# main.net
KiCad netlist of a schematic drawn in EAGLE
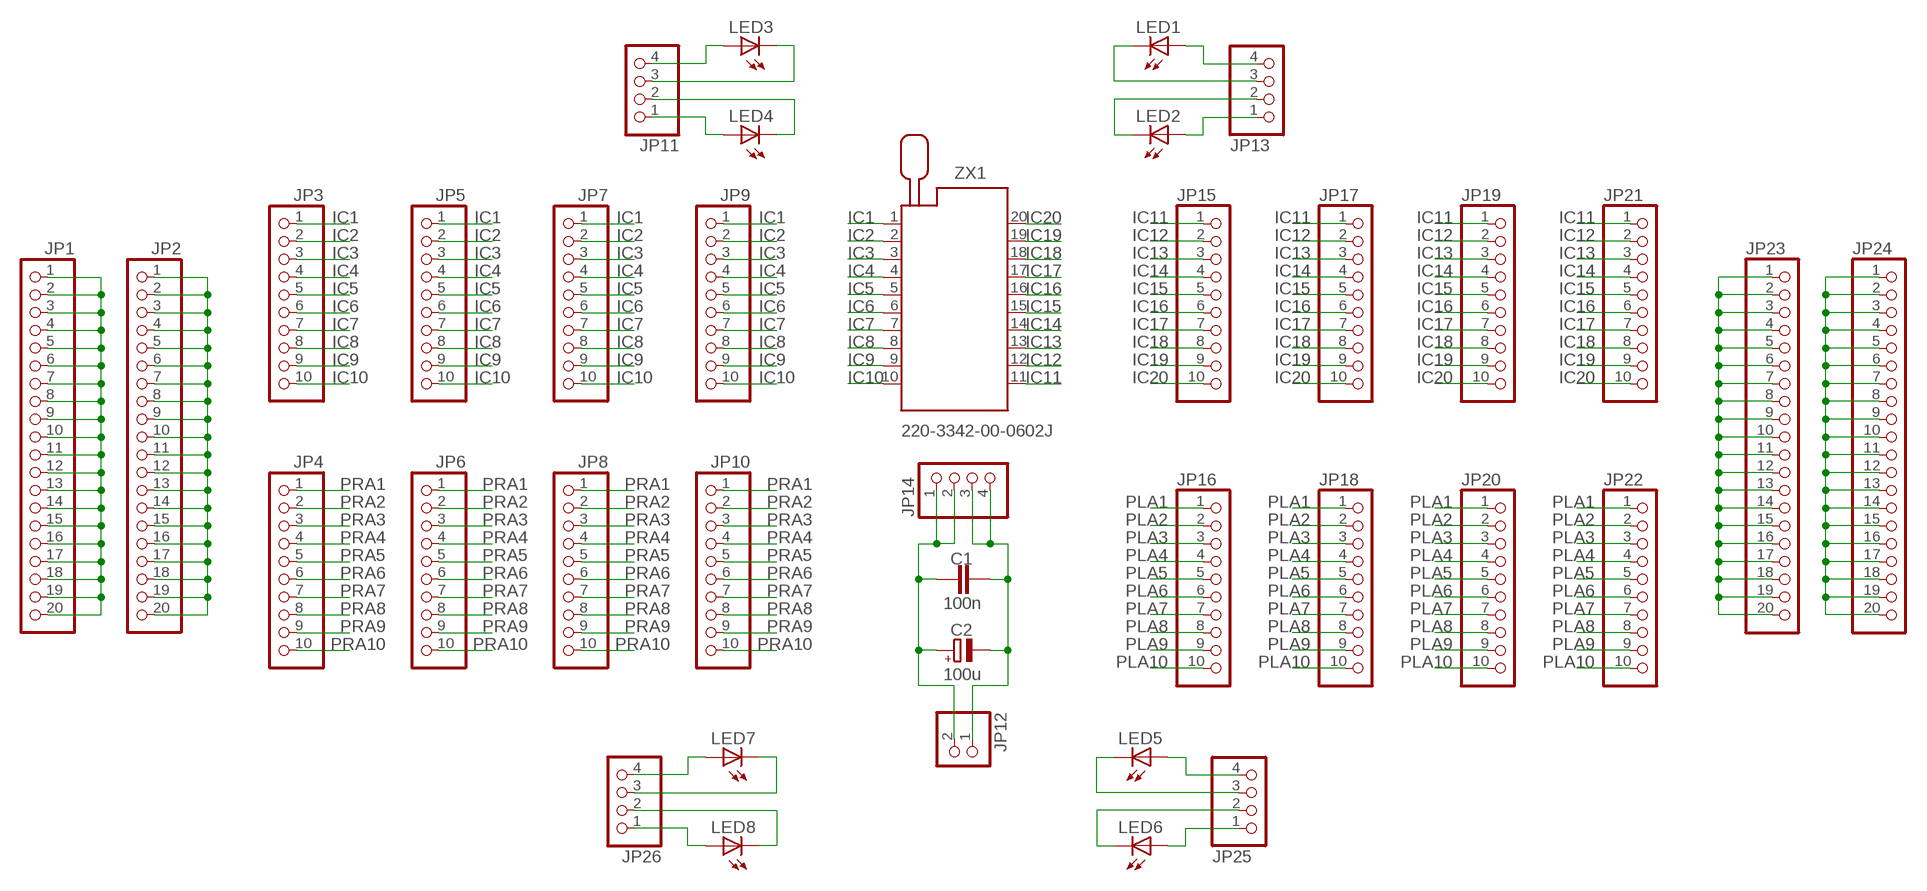
[diagram p0: schematic, sheet 1]

(export (version "E")
  (design (tool "Eeschema 10.0.6"))
  (components
    (comp (ref "C1")
      (value "100n")
      (footprint "eagle-import:C1206")
      (libsource (lib "eagle-import") (part "C-EUC1206"))
    )
    (comp (ref "C2")
      (value "100u")
      (footprint "eagle-import:SMC_A")
      (libsource (lib "eagle-import") (part "CPOL-EUSMCA"))
    )
    (comp (ref "JP1")
      (value "PINHD-1X20")
      (footprint "eagle-import:1X20")
      (libsource (lib "eagle-import") (part "PINHD-1X20"))
    )
    (comp (ref "JP2")
      (value "PINHD-1X20")
      (footprint "eagle-import:1X20")
      (libsource (lib "eagle-import") (part "PINHD-1X20"))
    )
    (comp (ref "JP3")
      (value "PINHD-1X10")
      (footprint "eagle-import:1X10")
      (libsource (lib "eagle-import") (part "PINHD-1X10"))
    )
    (comp (ref "JP4")
      (value "PINHD-1X10")
      (footprint "eagle-import:1X10")
      (libsource (lib "eagle-import") (part "PINHD-1X10"))
    )
    (comp (ref "JP5")
      (value "PINHD-1X10")
      (footprint "eagle-import:1X10")
      (libsource (lib "eagle-import") (part "PINHD-1X10"))
    )
    (comp (ref "JP6")
      (value "PINHD-1X10")
      (footprint "eagle-import:1X10")
      (libsource (lib "eagle-import") (part "PINHD-1X10"))
    )
    (comp (ref "JP7")
      (value "PINHD-1X10")
      (footprint "eagle-import:1X10")
      (libsource (lib "eagle-import") (part "PINHD-1X10"))
    )
    (comp (ref "JP8")
      (value "PINHD-1X10")
      (footprint "eagle-import:1X10")
      (libsource (lib "eagle-import") (part "PINHD-1X10"))
    )
    (comp (ref "JP9")
      (value "PINHD-1X10")
      (footprint "eagle-import:1X10")
      (libsource (lib "eagle-import") (part "PINHD-1X10"))
    )
    (comp (ref "JP10")
      (value "PINHD-1X10")
      (footprint "eagle-import:1X10")
      (libsource (lib "eagle-import") (part "PINHD-1X10"))
    )
    (comp (ref "JP11")
      (value "PINHD-1X4")
      (footprint "eagle-import:1X04")
      (libsource (lib "eagle-import") (part "PINHD-1X4"))
    )
    (comp (ref "JP12")
      (value "PINHD-1X2/90")
      (footprint "eagle-import:1X02_90")
      (libsource (lib "eagle-import") (part "PINHD-1X2/90"))
    )
    (comp (ref "JP13")
      (value "PINHD-1X4")
      (footprint "eagle-import:1X04")
      (libsource (lib "eagle-import") (part "PINHD-1X4"))
    )
    (comp (ref "JP14")
      (value "PINHD-1X4")
      (footprint "eagle-import:1X04")
      (libsource (lib "eagle-import") (part "PINHD-1X4"))
    )
    (comp (ref "JP15")
      (value "PINHD-1X10")
      (footprint "eagle-import:1X10")
      (libsource (lib "eagle-import") (part "PINHD-1X10"))
    )
    (comp (ref "JP16")
      (value "PINHD-1X10")
      (footprint "eagle-import:1X10")
      (libsource (lib "eagle-import") (part "PINHD-1X10"))
    )
    (comp (ref "JP17")
      (value "PINHD-1X10")
      (footprint "eagle-import:1X10")
      (libsource (lib "eagle-import") (part "PINHD-1X10"))
    )
    (comp (ref "JP18")
      (value "PINHD-1X10")
      (footprint "eagle-import:1X10")
      (libsource (lib "eagle-import") (part "PINHD-1X10"))
    )
    (comp (ref "JP19")
      (value "PINHD-1X10")
      (footprint "eagle-import:1X10")
      (libsource (lib "eagle-import") (part "PINHD-1X10"))
    )
    (comp (ref "JP20")
      (value "PINHD-1X10")
      (footprint "eagle-import:1X10")
      (libsource (lib "eagle-import") (part "PINHD-1X10"))
    )
    (comp (ref "JP21")
      (value "PINHD-1X10")
      (footprint "eagle-import:1X10")
      (libsource (lib "eagle-import") (part "PINHD-1X10"))
    )
    (comp (ref "JP22")
      (value "PINHD-1X10")
      (footprint "eagle-import:1X10")
      (libsource (lib "eagle-import") (part "PINHD-1X10"))
    )
    (comp (ref "JP23")
      (value "PINHD-1X20")
      (footprint "eagle-import:1X20")
      (libsource (lib "eagle-import") (part "PINHD-1X20"))
    )
    (comp (ref "JP24")
      (value "PINHD-1X20")
      (footprint "eagle-import:1X20")
      (libsource (lib "eagle-import") (part "PINHD-1X20"))
    )
    (comp (ref "JP25")
      (value "PINHD-1X4")
      (footprint "eagle-import:1X04")
      (libsource (lib "eagle-import") (part "PINHD-1X4"))
    )
    (comp (ref "JP26")
      (value "PINHD-1X4")
      (footprint "eagle-import:1X04")
      (libsource (lib "eagle-import") (part "PINHD-1X4"))
    )
    (comp (ref "LED1")
      (value "LEDSFH482")
      (footprint "eagle-import:SFH482")
      (libsource (lib "eagle-import") (part "LEDSFH482"))
    )
    (comp (ref "LED2")
      (value "LEDSFH482")
      (footprint "eagle-import:SFH482")
      (libsource (lib "eagle-import") (part "LEDSFH482"))
    )
    (comp (ref "LED3")
      (value "LEDSFH482")
      (footprint "eagle-import:SFH482")
      (libsource (lib "eagle-import") (part "LEDSFH482"))
    )
    (comp (ref "LED4")
      (value "LEDSFH482")
      (footprint "eagle-import:SFH482")
      (libsource (lib "eagle-import") (part "LEDSFH482"))
    )
    (comp (ref "LED5")
      (value "LEDSFH482")
      (footprint "eagle-import:SFH482")
      (libsource (lib "eagle-import") (part "LEDSFH482"))
    )
    (comp (ref "LED6")
      (value "LEDSFH482")
      (footprint "eagle-import:SFH482")
      (libsource (lib "eagle-import") (part "LEDSFH482"))
    )
    (comp (ref "LED7")
      (value "LEDSFH482")
      (footprint "eagle-import:SFH482")
      (libsource (lib "eagle-import") (part "LEDSFH482"))
    )
    (comp (ref "LED8")
      (value "LEDSFH482")
      (footprint "eagle-import:SFH482")
      (libsource (lib "eagle-import") (part "LEDSFH482"))
    )
    (comp (ref "ZX1")
      (value "220-3342-00-0602J")
      (footprint "eagle-import:220-3342-00-0602J")
      (fields (field (name "MF") "3M"))
      (libsource (lib "eagle-import") (part "220-3342-00-0602J"))
    )
  )
  (nets
    (net (code "1") (name "/IC1") (class "Default")
      (node (ref "JP3") (pin "1") (pinfunction "1_1") (pintype "passive"))
      (node (ref "JP5") (pin "1") (pinfunction "1_1") (pintype "passive"))
      (node (ref "JP7") (pin "1") (pinfunction "1_1") (pintype "passive"))
      (node (ref "JP9") (pin "1") (pinfunction "1_1") (pintype "passive"))
      (node (ref "ZX1") (pin "1") (pinfunction "1_1") (pintype "passive"))
    )
    (net (code "2") (name "/IC2") (class "Default")
      (node (ref "JP3") (pin "2") (pinfunction "2_2") (pintype "passive"))
      (node (ref "JP5") (pin "2") (pinfunction "2_2") (pintype "passive"))
      (node (ref "JP7") (pin "2") (pinfunction "2_2") (pintype "passive"))
      (node (ref "JP9") (pin "2") (pinfunction "2_2") (pintype "passive"))
      (node (ref "ZX1") (pin "2") (pinfunction "2_2") (pintype "passive"))
    )
    (net (code "3") (name "/IC3") (class "Default")
      (node (ref "JP3") (pin "3") (pinfunction "3_3") (pintype "passive"))
      (node (ref "JP5") (pin "3") (pinfunction "3_3") (pintype "passive"))
      (node (ref "JP7") (pin "3") (pinfunction "3_3") (pintype "passive"))
      (node (ref "JP9") (pin "3") (pinfunction "3_3") (pintype "passive"))
      (node (ref "ZX1") (pin "3") (pinfunction "3_3") (pintype "passive"))
    )
    (net (code "4") (name "/IC4") (class "Default")
      (node (ref "JP3") (pin "4") (pinfunction "4_4") (pintype "passive"))
      (node (ref "JP5") (pin "4") (pinfunction "4_4") (pintype "passive"))
      (node (ref "JP7") (pin "4") (pinfunction "4_4") (pintype "passive"))
      (node (ref "JP9") (pin "4") (pinfunction "4_4") (pintype "passive"))
      (node (ref "ZX1") (pin "4") (pinfunction "4_4") (pintype "passive"))
    )
    (net (code "5") (name "/IC5") (class "Default")
      (node (ref "JP3") (pin "5") (pinfunction "5_5") (pintype "passive"))
      (node (ref "JP5") (pin "5") (pinfunction "5_5") (pintype "passive"))
      (node (ref "JP7") (pin "5") (pinfunction "5_5") (pintype "passive"))
      (node (ref "JP9") (pin "5") (pinfunction "5_5") (pintype "passive"))
      (node (ref "ZX1") (pin "5") (pinfunction "5_5") (pintype "passive"))
    )
    (net (code "6") (name "/IC6") (class "Default")
      (node (ref "JP3") (pin "6") (pinfunction "6_6") (pintype "passive"))
      (node (ref "JP5") (pin "6") (pinfunction "6_6") (pintype "passive"))
      (node (ref "JP7") (pin "6") (pinfunction "6_6") (pintype "passive"))
      (node (ref "JP9") (pin "6") (pinfunction "6_6") (pintype "passive"))
      (node (ref "ZX1") (pin "6") (pinfunction "6_6") (pintype "passive"))
    )
    (net (code "7") (name "/IC7") (class "Default")
      (node (ref "JP3") (pin "7") (pinfunction "7_7") (pintype "passive"))
      (node (ref "JP5") (pin "7") (pinfunction "7_7") (pintype "passive"))
      (node (ref "JP7") (pin "7") (pinfunction "7_7") (pintype "passive"))
      (node (ref "JP9") (pin "7") (pinfunction "7_7") (pintype "passive"))
      (node (ref "ZX1") (pin "7") (pinfunction "7_7") (pintype "passive"))
    )
    (net (code "8") (name "/IC8") (class "Default")
      (node (ref "JP3") (pin "8") (pinfunction "8_8") (pintype "passive"))
      (node (ref "JP5") (pin "8") (pinfunction "8_8") (pintype "passive"))
      (node (ref "JP7") (pin "8") (pinfunction "8_8") (pintype "passive"))
      (node (ref "JP9") (pin "8") (pinfunction "8_8") (pintype "passive"))
      (node (ref "ZX1") (pin "8") (pinfunction "8_8") (pintype "passive"))
    )
    (net (code "9") (name "/IC9") (class "Default")
      (node (ref "JP3") (pin "9") (pinfunction "9_9") (pintype "passive"))
      (node (ref "JP5") (pin "9") (pinfunction "9_9") (pintype "passive"))
      (node (ref "JP7") (pin "9") (pinfunction "9_9") (pintype "passive"))
      (node (ref "JP9") (pin "9") (pinfunction "9_9") (pintype "passive"))
      (node (ref "ZX1") (pin "9") (pinfunction "9_9") (pintype "passive"))
    )
    (net (code "10") (name "/IC10") (class "Default")
      (node (ref "JP3") (pin "10") (pinfunction "10_10") (pintype "passive"))
      (node (ref "JP5") (pin "10") (pinfunction "10_10") (pintype "passive"))
      (node (ref "JP7") (pin "10") (pinfunction "10_10") (pintype "passive"))
      (node (ref "JP9") (pin "10") (pinfunction "10_10") (pintype "passive"))
      (node (ref "ZX1") (pin "10") (pinfunction "10_10") (pintype "passive"))
    )
    (net (code "11") (name "/IC11") (class "Default")
      (node (ref "JP15") (pin "1") (pinfunction "1_1") (pintype "passive"))
      (node (ref "JP17") (pin "1") (pinfunction "1_1") (pintype "passive"))
      (node (ref "JP19") (pin "1") (pinfunction "1_1") (pintype "passive"))
      (node (ref "JP21") (pin "1") (pinfunction "1_1") (pintype "passive"))
      (node (ref "ZX1") (pin "11") (pinfunction "11_11") (pintype "passive"))
    )
    (net (code "12") (name "/IC12") (class "Default")
      (node (ref "JP15") (pin "2") (pinfunction "2_2") (pintype "passive"))
      (node (ref "JP17") (pin "2") (pinfunction "2_2") (pintype "passive"))
      (node (ref "JP19") (pin "2") (pinfunction "2_2") (pintype "passive"))
      (node (ref "JP21") (pin "2") (pinfunction "2_2") (pintype "passive"))
      (node (ref "ZX1") (pin "12") (pinfunction "12_12") (pintype "passive"))
    )
    (net (code "13") (name "/IC13") (class "Default")
      (node (ref "JP15") (pin "3") (pinfunction "3_3") (pintype "passive"))
      (node (ref "JP17") (pin "3") (pinfunction "3_3") (pintype "passive"))
      (node (ref "JP19") (pin "3") (pinfunction "3_3") (pintype "passive"))
      (node (ref "JP21") (pin "3") (pinfunction "3_3") (pintype "passive"))
      (node (ref "ZX1") (pin "13") (pinfunction "13_13") (pintype "passive"))
    )
    (net (code "14") (name "/IC14") (class "Default")
      (node (ref "JP15") (pin "4") (pinfunction "4_4") (pintype "passive"))
      (node (ref "JP17") (pin "4") (pinfunction "4_4") (pintype "passive"))
      (node (ref "JP19") (pin "4") (pinfunction "4_4") (pintype "passive"))
      (node (ref "JP21") (pin "4") (pinfunction "4_4") (pintype "passive"))
      (node (ref "ZX1") (pin "14") (pinfunction "14_14") (pintype "passive"))
    )
    (net (code "15") (name "/IC15") (class "Default")
      (node (ref "JP15") (pin "5") (pinfunction "5_5") (pintype "passive"))
      (node (ref "JP17") (pin "5") (pinfunction "5_5") (pintype "passive"))
      (node (ref "JP19") (pin "5") (pinfunction "5_5") (pintype "passive"))
      (node (ref "JP21") (pin "5") (pinfunction "5_5") (pintype "passive"))
      (node (ref "ZX1") (pin "15") (pinfunction "15_15") (pintype "passive"))
    )
    (net (code "16") (name "/IC16") (class "Default")
      (node (ref "JP15") (pin "6") (pinfunction "6_6") (pintype "passive"))
      (node (ref "JP17") (pin "6") (pinfunction "6_6") (pintype "passive"))
      (node (ref "JP19") (pin "6") (pinfunction "6_6") (pintype "passive"))
      (node (ref "JP21") (pin "6") (pinfunction "6_6") (pintype "passive"))
      (node (ref "ZX1") (pin "16") (pinfunction "16_16") (pintype "passive"))
    )
    (net (code "17") (name "/IC17") (class "Default")
      (node (ref "JP15") (pin "7") (pinfunction "7_7") (pintype "passive"))
      (node (ref "JP17") (pin "7") (pinfunction "7_7") (pintype "passive"))
      (node (ref "JP19") (pin "7") (pinfunction "7_7") (pintype "passive"))
      (node (ref "JP21") (pin "7") (pinfunction "7_7") (pintype "passive"))
      (node (ref "ZX1") (pin "17") (pinfunction "17_17") (pintype "passive"))
    )
    (net (code "18") (name "/IC18") (class "Default")
      (node (ref "JP15") (pin "8") (pinfunction "8_8") (pintype "passive"))
      (node (ref "JP17") (pin "8") (pinfunction "8_8") (pintype "passive"))
      (node (ref "JP19") (pin "8") (pinfunction "8_8") (pintype "passive"))
      (node (ref "JP21") (pin "8") (pinfunction "8_8") (pintype "passive"))
      (node (ref "ZX1") (pin "18") (pinfunction "18_18") (pintype "passive"))
    )
    (net (code "19") (name "/IC19") (class "Default")
      (node (ref "JP15") (pin "9") (pinfunction "9_9") (pintype "passive"))
      (node (ref "JP17") (pin "9") (pinfunction "9_9") (pintype "passive"))
      (node (ref "JP19") (pin "9") (pinfunction "9_9") (pintype "passive"))
      (node (ref "JP21") (pin "9") (pinfunction "9_9") (pintype "passive"))
      (node (ref "ZX1") (pin "19") (pinfunction "19_19") (pintype "passive"))
    )
    (net (code "20") (name "/IC20") (class "Default")
      (node (ref "JP15") (pin "10") (pinfunction "10_10") (pintype "passive"))
      (node (ref "JP17") (pin "10") (pinfunction "10_10") (pintype "passive"))
      (node (ref "JP19") (pin "10") (pinfunction "10_10") (pintype "passive"))
      (node (ref "JP21") (pin "10") (pinfunction "10_10") (pintype "passive"))
      (node (ref "ZX1") (pin "20") (pinfunction "20_20") (pintype "passive"))
    )
    (net (code "21") (name "/PLA1") (class "Default")
      (node (ref "JP16") (pin "1") (pinfunction "1_1") (pintype "passive"))
      (node (ref "JP18") (pin "1") (pinfunction "1_1") (pintype "passive"))
      (node (ref "JP20") (pin "1") (pinfunction "1_1") (pintype "passive"))
      (node (ref "JP22") (pin "1") (pinfunction "1_1") (pintype "passive"))
    )
    (net (code "22") (name "/PLA2") (class "Default")
      (node (ref "JP16") (pin "2") (pinfunction "2_2") (pintype "passive"))
      (node (ref "JP18") (pin "2") (pinfunction "2_2") (pintype "passive"))
      (node (ref "JP20") (pin "2") (pinfunction "2_2") (pintype "passive"))
      (node (ref "JP22") (pin "2") (pinfunction "2_2") (pintype "passive"))
    )
    (net (code "23") (name "/PLA3") (class "Default")
      (node (ref "JP16") (pin "3") (pinfunction "3_3") (pintype "passive"))
      (node (ref "JP18") (pin "3") (pinfunction "3_3") (pintype "passive"))
      (node (ref "JP20") (pin "3") (pinfunction "3_3") (pintype "passive"))
      (node (ref "JP22") (pin "3") (pinfunction "3_3") (pintype "passive"))
    )
    (net (code "24") (name "/PLA4") (class "Default")
      (node (ref "JP16") (pin "4") (pinfunction "4_4") (pintype "passive"))
      (node (ref "JP18") (pin "4") (pinfunction "4_4") (pintype "passive"))
      (node (ref "JP20") (pin "4") (pinfunction "4_4") (pintype "passive"))
      (node (ref "JP22") (pin "4") (pinfunction "4_4") (pintype "passive"))
    )
    (net (code "25") (name "/PLA5") (class "Default")
      (node (ref "JP16") (pin "5") (pinfunction "5_5") (pintype "passive"))
      (node (ref "JP18") (pin "5") (pinfunction "5_5") (pintype "passive"))
      (node (ref "JP20") (pin "5") (pinfunction "5_5") (pintype "passive"))
      (node (ref "JP22") (pin "5") (pinfunction "5_5") (pintype "passive"))
    )
    (net (code "26") (name "/PLA6") (class "Default")
      (node (ref "JP16") (pin "6") (pinfunction "6_6") (pintype "passive"))
      (node (ref "JP18") (pin "6") (pinfunction "6_6") (pintype "passive"))
      (node (ref "JP20") (pin "6") (pinfunction "6_6") (pintype "passive"))
      (node (ref "JP22") (pin "6") (pinfunction "6_6") (pintype "passive"))
    )
    (net (code "27") (name "/PLA7") (class "Default")
      (node (ref "JP16") (pin "7") (pinfunction "7_7") (pintype "passive"))
      (node (ref "JP18") (pin "7") (pinfunction "7_7") (pintype "passive"))
      (node (ref "JP20") (pin "7") (pinfunction "7_7") (pintype "passive"))
      (node (ref "JP22") (pin "7") (pinfunction "7_7") (pintype "passive"))
    )
    (net (code "28") (name "/PLA8") (class "Default")
      (node (ref "JP16") (pin "8") (pinfunction "8_8") (pintype "passive"))
      (node (ref "JP18") (pin "8") (pinfunction "8_8") (pintype "passive"))
      (node (ref "JP20") (pin "8") (pinfunction "8_8") (pintype "passive"))
      (node (ref "JP22") (pin "8") (pinfunction "8_8") (pintype "passive"))
    )
    (net (code "29") (name "/PLA9") (class "Default")
      (node (ref "JP16") (pin "9") (pinfunction "9_9") (pintype "passive"))
      (node (ref "JP18") (pin "9") (pinfunction "9_9") (pintype "passive"))
      (node (ref "JP20") (pin "9") (pinfunction "9_9") (pintype "passive"))
      (node (ref "JP22") (pin "9") (pinfunction "9_9") (pintype "passive"))
    )
    (net (code "30") (name "/PLA10") (class "Default")
      (node (ref "JP16") (pin "10") (pinfunction "10_10") (pintype "passive"))
      (node (ref "JP18") (pin "10") (pinfunction "10_10") (pintype "passive"))
      (node (ref "JP20") (pin "10") (pinfunction "10_10") (pintype "passive"))
      (node (ref "JP22") (pin "10") (pinfunction "10_10") (pintype "passive"))
    )
    (net (code "31") (name "/PRA1") (class "Default")
      (node (ref "JP10") (pin "1") (pinfunction "1_1") (pintype "passive"))
      (node (ref "JP4") (pin "1") (pinfunction "1_1") (pintype "passive"))
      (node (ref "JP6") (pin "1") (pinfunction "1_1") (pintype "passive"))
      (node (ref "JP8") (pin "1") (pinfunction "1_1") (pintype "passive"))
    )
    (net (code "32") (name "/PRA2") (class "Default")
      (node (ref "JP10") (pin "2") (pinfunction "2_2") (pintype "passive"))
      (node (ref "JP4") (pin "2") (pinfunction "2_2") (pintype "passive"))
      (node (ref "JP6") (pin "2") (pinfunction "2_2") (pintype "passive"))
      (node (ref "JP8") (pin "2") (pinfunction "2_2") (pintype "passive"))
    )
    (net (code "33") (name "/PRA3") (class "Default")
      (node (ref "JP10") (pin "3") (pinfunction "3_3") (pintype "passive"))
      (node (ref "JP4") (pin "3") (pinfunction "3_3") (pintype "passive"))
      (node (ref "JP6") (pin "3") (pinfunction "3_3") (pintype "passive"))
      (node (ref "JP8") (pin "3") (pinfunction "3_3") (pintype "passive"))
    )
    (net (code "34") (name "/PRA4") (class "Default")
      (node (ref "JP10") (pin "4") (pinfunction "4_4") (pintype "passive"))
      (node (ref "JP4") (pin "4") (pinfunction "4_4") (pintype "passive"))
      (node (ref "JP6") (pin "4") (pinfunction "4_4") (pintype "passive"))
      (node (ref "JP8") (pin "4") (pinfunction "4_4") (pintype "passive"))
    )
    (net (code "35") (name "/PRA5") (class "Default")
      (node (ref "JP10") (pin "5") (pinfunction "5_5") (pintype "passive"))
      (node (ref "JP4") (pin "5") (pinfunction "5_5") (pintype "passive"))
      (node (ref "JP6") (pin "5") (pinfunction "5_5") (pintype "passive"))
      (node (ref "JP8") (pin "5") (pinfunction "5_5") (pintype "passive"))
    )
    (net (code "36") (name "/PRA6") (class "Default")
      (node (ref "JP10") (pin "6") (pinfunction "6_6") (pintype "passive"))
      (node (ref "JP4") (pin "6") (pinfunction "6_6") (pintype "passive"))
      (node (ref "JP6") (pin "6") (pinfunction "6_6") (pintype "passive"))
      (node (ref "JP8") (pin "6") (pinfunction "6_6") (pintype "passive"))
    )
    (net (code "37") (name "/PRA7") (class "Default")
      (node (ref "JP10") (pin "7") (pinfunction "7_7") (pintype "passive"))
      (node (ref "JP4") (pin "7") (pinfunction "7_7") (pintype "passive"))
      (node (ref "JP6") (pin "7") (pinfunction "7_7") (pintype "passive"))
      (node (ref "JP8") (pin "7") (pinfunction "7_7") (pintype "passive"))
    )
    (net (code "38") (name "/PRA8") (class "Default")
      (node (ref "JP10") (pin "8") (pinfunction "8_8") (pintype "passive"))
      (node (ref "JP4") (pin "8") (pinfunction "8_8") (pintype "passive"))
      (node (ref "JP6") (pin "8") (pinfunction "8_8") (pintype "passive"))
      (node (ref "JP8") (pin "8") (pinfunction "8_8") (pintype "passive"))
    )
    (net (code "39") (name "/PRA9") (class "Default")
      (node (ref "JP10") (pin "9") (pinfunction "9_9") (pintype "passive"))
      (node (ref "JP4") (pin "9") (pinfunction "9_9") (pintype "passive"))
      (node (ref "JP6") (pin "9") (pinfunction "9_9") (pintype "passive"))
      (node (ref "JP8") (pin "9") (pinfunction "9_9") (pintype "passive"))
    )
    (net (code "40") (name "/PRA10") (class "Default")
      (node (ref "JP10") (pin "10") (pinfunction "10_10") (pintype "passive"))
      (node (ref "JP4") (pin "10") (pinfunction "10_10") (pintype "passive"))
      (node (ref "JP6") (pin "10") (pinfunction "10_10") (pintype "passive"))
      (node (ref "JP8") (pin "10") (pinfunction "10_10") (pintype "passive"))
    )
    (net (code "41") (name "Net-(C1-Pad1)") (class "Default")
      (node (ref "C1") (pin "1") (pinfunction "1_1") (pintype "passive"))
      (node (ref "C2") (pin "+") (pinfunction "+_+") (pintype "passive"))
      (node (ref "JP12") (pin "2") (pinfunction "2_2") (pintype "passive"))
      (node (ref "JP14") (pin "1") (pinfunction "1_1") (pintype "passive"))
      (node (ref "JP14") (pin "2") (pinfunction "2_2") (pintype "passive"))
    )
    (net (code "42") (name "Net-(C1-Pad2)") (class "Default")
      (node (ref "C1") (pin "2") (pinfunction "2_2") (pintype "passive"))
      (node (ref "C2") (pin "-") (pinfunction "-_-") (pintype "passive"))
      (node (ref "JP12") (pin "1") (pinfunction "1_1") (pintype "passive"))
      (node (ref "JP14") (pin "3") (pinfunction "3_3") (pintype "passive"))
      (node (ref "JP14") (pin "4") (pinfunction "4_4") (pintype "passive"))
    )
    (net (code "43") (name "Net-(JP1-Pad1)") (class "Default")
      (node (ref "JP1") (pin "1") (pinfunction "1_1") (pintype "passive"))
      (node (ref "JP1") (pin "10") (pinfunction "10_10") (pintype "passive"))
      (node (ref "JP1") (pin "11") (pinfunction "11_11") (pintype "passive"))
      (node (ref "JP1") (pin "12") (pinfunction "12_12") (pintype "passive"))
      (node (ref "JP1") (pin "13") (pinfunction "13_13") (pintype "passive"))
      (node (ref "JP1") (pin "14") (pinfunction "14_14") (pintype "passive"))
      (node (ref "JP1") (pin "15") (pinfunction "15_15") (pintype "passive"))
      (node (ref "JP1") (pin "16") (pinfunction "16_16") (pintype "passive"))
      (node (ref "JP1") (pin "17") (pinfunction "17_17") (pintype "passive"))
      (node (ref "JP1") (pin "18") (pinfunction "18_18") (pintype "passive"))
      (node (ref "JP1") (pin "19") (pinfunction "19_19") (pintype "passive"))
      (node (ref "JP1") (pin "2") (pinfunction "2_2") (pintype "passive"))
      (node (ref "JP1") (pin "20") (pinfunction "20_20") (pintype "passive"))
      (node (ref "JP1") (pin "3") (pinfunction "3_3") (pintype "passive"))
      (node (ref "JP1") (pin "4") (pinfunction "4_4") (pintype "passive"))
      (node (ref "JP1") (pin "5") (pinfunction "5_5") (pintype "passive"))
      (node (ref "JP1") (pin "6") (pinfunction "6_6") (pintype "passive"))
      (node (ref "JP1") (pin "7") (pinfunction "7_7") (pintype "passive"))
      (node (ref "JP1") (pin "8") (pinfunction "8_8") (pintype "passive"))
      (node (ref "JP1") (pin "9") (pinfunction "9_9") (pintype "passive"))
    )
    (net (code "44") (name "Net-(JP2-Pad1)") (class "Default")
      (node (ref "JP2") (pin "1") (pinfunction "1_1") (pintype "passive"))
      (node (ref "JP2") (pin "10") (pinfunction "10_10") (pintype "passive"))
      (node (ref "JP2") (pin "11") (pinfunction "11_11") (pintype "passive"))
      (node (ref "JP2") (pin "12") (pinfunction "12_12") (pintype "passive"))
      (node (ref "JP2") (pin "13") (pinfunction "13_13") (pintype "passive"))
      (node (ref "JP2") (pin "14") (pinfunction "14_14") (pintype "passive"))
      (node (ref "JP2") (pin "15") (pinfunction "15_15") (pintype "passive"))
      (node (ref "JP2") (pin "16") (pinfunction "16_16") (pintype "passive"))
      (node (ref "JP2") (pin "17") (pinfunction "17_17") (pintype "passive"))
      (node (ref "JP2") (pin "18") (pinfunction "18_18") (pintype "passive"))
      (node (ref "JP2") (pin "19") (pinfunction "19_19") (pintype "passive"))
      (node (ref "JP2") (pin "2") (pinfunction "2_2") (pintype "passive"))
      (node (ref "JP2") (pin "20") (pinfunction "20_20") (pintype "passive"))
      (node (ref "JP2") (pin "3") (pinfunction "3_3") (pintype "passive"))
      (node (ref "JP2") (pin "4") (pinfunction "4_4") (pintype "passive"))
      (node (ref "JP2") (pin "5") (pinfunction "5_5") (pintype "passive"))
      (node (ref "JP2") (pin "6") (pinfunction "6_6") (pintype "passive"))
      (node (ref "JP2") (pin "7") (pinfunction "7_7") (pintype "passive"))
      (node (ref "JP2") (pin "8") (pinfunction "8_8") (pintype "passive"))
      (node (ref "JP2") (pin "9") (pinfunction "9_9") (pintype "passive"))
    )
    (net (code "45") (name "Net-(JP11-Pad1)") (class "Default")
      (node (ref "JP11") (pin "1") (pinfunction "1_1") (pintype "passive"))
      (node (ref "LED4") (pin "A") (pinfunction "A_A") (pintype "passive"))
    )
    (net (code "46") (name "Net-(JP11-Pad4)") (class "Default")
      (node (ref "JP11") (pin "4") (pinfunction "4_4") (pintype "passive"))
      (node (ref "LED3") (pin "A") (pinfunction "A_A") (pintype "passive"))
    )
    (net (code "47") (name "Net-(JP13-Pad1)") (class "Default")
      (node (ref "JP13") (pin "1") (pinfunction "1_1") (pintype "passive"))
      (node (ref "LED2") (pin "A") (pinfunction "A_A") (pintype "passive"))
    )
    (net (code "48") (name "Net-(JP13-Pad4)") (class "Default")
      (node (ref "JP13") (pin "4") (pinfunction "4_4") (pintype "passive"))
      (node (ref "LED1") (pin "A") (pinfunction "A_A") (pintype "passive"))
    )
    (net (code "49") (name "Net-(JP23-Pad1)") (class "Default")
      (node (ref "JP23") (pin "1") (pinfunction "1_1") (pintype "passive"))
      (node (ref "JP23") (pin "10") (pinfunction "10_10") (pintype "passive"))
      (node (ref "JP23") (pin "11") (pinfunction "11_11") (pintype "passive"))
      (node (ref "JP23") (pin "12") (pinfunction "12_12") (pintype "passive"))
      (node (ref "JP23") (pin "13") (pinfunction "13_13") (pintype "passive"))
      (node (ref "JP23") (pin "14") (pinfunction "14_14") (pintype "passive"))
      (node (ref "JP23") (pin "15") (pinfunction "15_15") (pintype "passive"))
      (node (ref "JP23") (pin "16") (pinfunction "16_16") (pintype "passive"))
      (node (ref "JP23") (pin "17") (pinfunction "17_17") (pintype "passive"))
      (node (ref "JP23") (pin "18") (pinfunction "18_18") (pintype "passive"))
      (node (ref "JP23") (pin "19") (pinfunction "19_19") (pintype "passive"))
      (node (ref "JP23") (pin "2") (pinfunction "2_2") (pintype "passive"))
      (node (ref "JP23") (pin "20") (pinfunction "20_20") (pintype "passive"))
      (node (ref "JP23") (pin "3") (pinfunction "3_3") (pintype "passive"))
      (node (ref "JP23") (pin "4") (pinfunction "4_4") (pintype "passive"))
      (node (ref "JP23") (pin "5") (pinfunction "5_5") (pintype "passive"))
      (node (ref "JP23") (pin "6") (pinfunction "6_6") (pintype "passive"))
      (node (ref "JP23") (pin "7") (pinfunction "7_7") (pintype "passive"))
      (node (ref "JP23") (pin "8") (pinfunction "8_8") (pintype "passive"))
      (node (ref "JP23") (pin "9") (pinfunction "9_9") (pintype "passive"))
    )
    (net (code "50") (name "Net-(JP24-Pad1)") (class "Default")
      (node (ref "JP24") (pin "1") (pinfunction "1_1") (pintype "passive"))
      (node (ref "JP24") (pin "10") (pinfunction "10_10") (pintype "passive"))
      (node (ref "JP24") (pin "11") (pinfunction "11_11") (pintype "passive"))
      (node (ref "JP24") (pin "12") (pinfunction "12_12") (pintype "passive"))
      (node (ref "JP24") (pin "13") (pinfunction "13_13") (pintype "passive"))
      (node (ref "JP24") (pin "14") (pinfunction "14_14") (pintype "passive"))
      (node (ref "JP24") (pin "15") (pinfunction "15_15") (pintype "passive"))
      (node (ref "JP24") (pin "16") (pinfunction "16_16") (pintype "passive"))
      (node (ref "JP24") (pin "17") (pinfunction "17_17") (pintype "passive"))
      (node (ref "JP24") (pin "18") (pinfunction "18_18") (pintype "passive"))
      (node (ref "JP24") (pin "19") (pinfunction "19_19") (pintype "passive"))
      (node (ref "JP24") (pin "2") (pinfunction "2_2") (pintype "passive"))
      (node (ref "JP24") (pin "20") (pinfunction "20_20") (pintype "passive"))
      (node (ref "JP24") (pin "3") (pinfunction "3_3") (pintype "passive"))
      (node (ref "JP24") (pin "4") (pinfunction "4_4") (pintype "passive"))
      (node (ref "JP24") (pin "5") (pinfunction "5_5") (pintype "passive"))
      (node (ref "JP24") (pin "6") (pinfunction "6_6") (pintype "passive"))
      (node (ref "JP24") (pin "7") (pinfunction "7_7") (pintype "passive"))
      (node (ref "JP24") (pin "8") (pinfunction "8_8") (pintype "passive"))
      (node (ref "JP24") (pin "9") (pinfunction "9_9") (pintype "passive"))
    )
    (net (code "51") (name "Net-(JP25-Pad1)") (class "Default")
      (node (ref "JP25") (pin "1") (pinfunction "1_1") (pintype "passive"))
      (node (ref "LED6") (pin "A") (pinfunction "A_A") (pintype "passive"))
    )
    (net (code "52") (name "Net-(JP25-Pad4)") (class "Default")
      (node (ref "JP25") (pin "4") (pinfunction "4_4") (pintype "passive"))
      (node (ref "LED5") (pin "A") (pinfunction "A_A") (pintype "passive"))
    )
    (net (code "53") (name "Net-(JP26-Pad1)") (class "Default")
      (node (ref "JP26") (pin "1") (pinfunction "1_1") (pintype "passive"))
      (node (ref "LED8") (pin "A") (pinfunction "A_A") (pintype "passive"))
    )
    (net (code "54") (name "Net-(JP26-Pad4)") (class "Default")
      (node (ref "JP26") (pin "4") (pinfunction "4_4") (pintype "passive"))
      (node (ref "LED7") (pin "A") (pinfunction "A_A") (pintype "passive"))
    )
    (net (code "55") (name "Net-(LED1-C)") (class "Default")
      (node (ref "JP13") (pin "3") (pinfunction "3_3") (pintype "passive"))
      (node (ref "LED1") (pin "K") (pinfunction "C_K") (pintype "passive"))
    )
    (net (code "56") (name "Net-(LED2-C)") (class "Default")
      (node (ref "JP13") (pin "2") (pinfunction "2_2") (pintype "passive"))
      (node (ref "LED2") (pin "K") (pinfunction "C_K") (pintype "passive"))
    )
    (net (code "57") (name "Net-(LED3-C)") (class "Default")
      (node (ref "JP11") (pin "3") (pinfunction "3_3") (pintype "passive"))
      (node (ref "LED3") (pin "K") (pinfunction "C_K") (pintype "passive"))
    )
    (net (code "58") (name "Net-(LED4-C)") (class "Default")
      (node (ref "JP11") (pin "2") (pinfunction "2_2") (pintype "passive"))
      (node (ref "LED4") (pin "K") (pinfunction "C_K") (pintype "passive"))
    )
    (net (code "59") (name "Net-(LED5-C)") (class "Default")
      (node (ref "JP25") (pin "3") (pinfunction "3_3") (pintype "passive"))
      (node (ref "LED5") (pin "K") (pinfunction "C_K") (pintype "passive"))
    )
    (net (code "60") (name "Net-(LED6-C)") (class "Default")
      (node (ref "JP25") (pin "2") (pinfunction "2_2") (pintype "passive"))
      (node (ref "LED6") (pin "K") (pinfunction "C_K") (pintype "passive"))
    )
    (net (code "61") (name "Net-(LED7-C)") (class "Default")
      (node (ref "JP26") (pin "3") (pinfunction "3_3") (pintype "passive"))
      (node (ref "LED7") (pin "K") (pinfunction "C_K") (pintype "passive"))
    )
    (net (code "62") (name "Net-(LED8-C)") (class "Default")
      (node (ref "JP26") (pin "2") (pinfunction "2_2") (pintype "passive"))
      (node (ref "LED8") (pin "K") (pinfunction "C_K") (pintype "passive"))
    )
  )
)
